# Buttons.net
KiCad netlist of a schematic drawn in Altium Designer
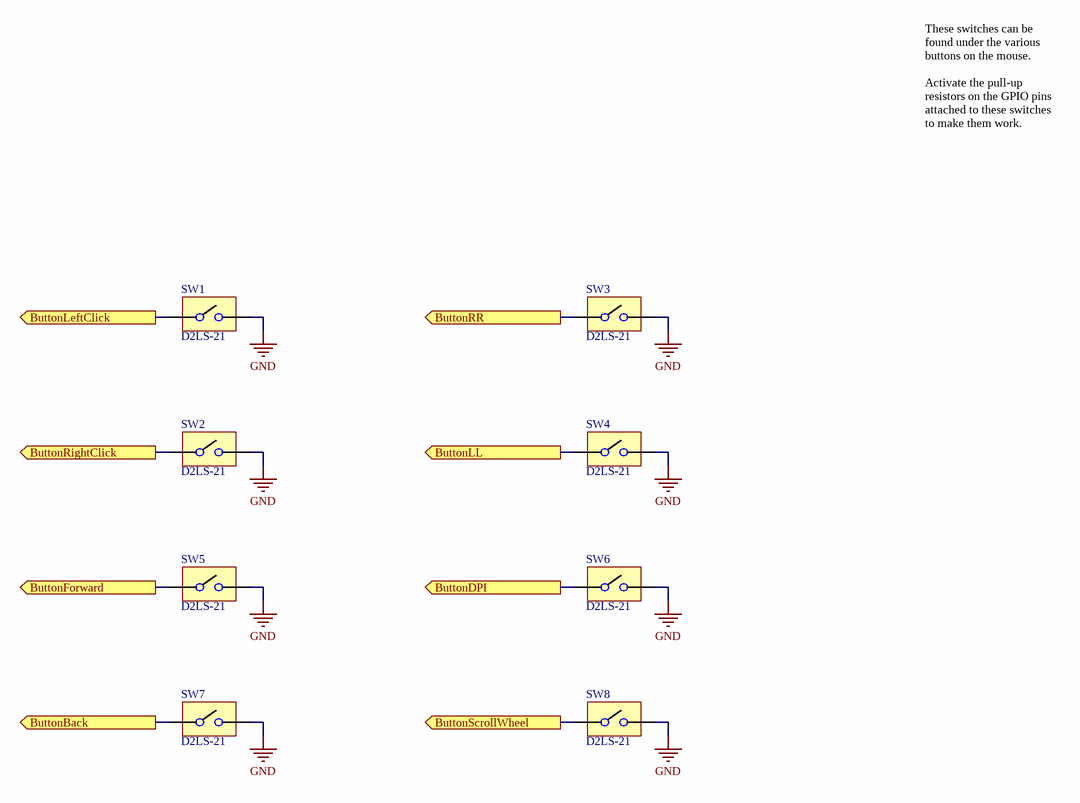
[diagram p0: Buttons.SchDoc]

(export (version "E")
  (design (tool "Eeschema 10.0.6"))
  (components
    (comp (ref "SW1")
      (value "D2LS-21")
      (footprint "D2LS-21")
      (description "Compact Surface-mounting Switch for long durability")
      (libsource (lib "Switches") (part "D2LS-21"))
    )
    (comp (ref "SW2")
      (value "D2LS-21")
      (footprint "D2LS-21")
      (description "Compact Surface-mounting Switch for long durability")
      (libsource (lib "Switches") (part "D2LS-21"))
    )
    (comp (ref "SW3")
      (value "D2LS-21")
      (footprint "D2LS-21")
      (description "Compact Surface-mounting Switch for long durability")
      (libsource (lib "Switches") (part "D2LS-21"))
    )
    (comp (ref "SW4")
      (value "D2LS-21")
      (footprint "D2LS-21")
      (description "Compact Surface-mounting Switch for long durability")
      (libsource (lib "Switches") (part "D2LS-21"))
    )
    (comp (ref "SW5")
      (value "D2LS-21")
      (footprint "D2LS-21")
      (description "Compact Surface-mounting Switch for long durability")
      (libsource (lib "Switches") (part "D2LS-21"))
    )
    (comp (ref "SW6")
      (value "D2LS-21")
      (footprint "D2LS-21")
      (description "Compact Surface-mounting Switch for long durability")
      (libsource (lib "Switches") (part "D2LS-21"))
    )
    (comp (ref "SW7")
      (value "D2LS-21")
      (footprint "D2LS-21")
      (description "Compact Surface-mounting Switch for long durability")
      (libsource (lib "Switches") (part "D2LS-21"))
    )
    (comp (ref "SW8")
      (value "D2LS-21")
      (footprint "D2LS-21")
      (description "Compact Surface-mounting Switch for long durability")
      (libsource (lib "Switches") (part "D2LS-21"))
    )
  )
  (nets
    (net (code "1") (name "/ButtonBack") (class "Default")
      (node (ref "SW7") (pin "A") (pinfunction "A_A") (pintype "passive"))
    )
    (net (code "2") (name "/ButtonDPI") (class "Default")
      (node (ref "SW6") (pin "A") (pinfunction "A_A") (pintype "passive"))
    )
    (net (code "3") (name "/ButtonForward") (class "Default")
      (node (ref "SW5") (pin "A") (pinfunction "A_A") (pintype "passive"))
    )
    (net (code "4") (name "/ButtonLL") (class "Default")
      (node (ref "SW4") (pin "A") (pinfunction "A_A") (pintype "passive"))
    )
    (net (code "5") (name "/ButtonLeftClick") (class "Default")
      (node (ref "SW1") (pin "A") (pinfunction "A_A") (pintype "passive"))
    )
    (net (code "6") (name "/ButtonRR") (class "Default")
      (node (ref "SW3") (pin "A") (pinfunction "A_A") (pintype "passive"))
    )
    (net (code "7") (name "/ButtonRightClick") (class "Default")
      (node (ref "SW2") (pin "A") (pinfunction "A_A") (pintype "passive"))
    )
    (net (code "8") (name "/ButtonScrollWheel") (class "Default")
      (node (ref "SW8") (pin "A") (pinfunction "A_A") (pintype "passive"))
    )
    (net (code "9") (name "GND") (class "Default")
      (node (ref "SW1") (pin "B") (pinfunction "B_B") (pintype "passive"))
      (node (ref "SW2") (pin "B") (pinfunction "B_B") (pintype "passive"))
      (node (ref "SW3") (pin "B") (pinfunction "B_B") (pintype "passive"))
      (node (ref "SW4") (pin "B") (pinfunction "B_B") (pintype "passive"))
      (node (ref "SW5") (pin "B") (pinfunction "B_B") (pintype "passive"))
      (node (ref "SW6") (pin "B") (pinfunction "B_B") (pintype "passive"))
      (node (ref "SW7") (pin "B") (pinfunction "B_B") (pintype "passive"))
      (node (ref "SW8") (pin "B") (pinfunction "B_B") (pintype "passive"))
    )
  )
)
